# Motor_Encoders.net
KiCad netlist of a schematic drawn in Altium Designer
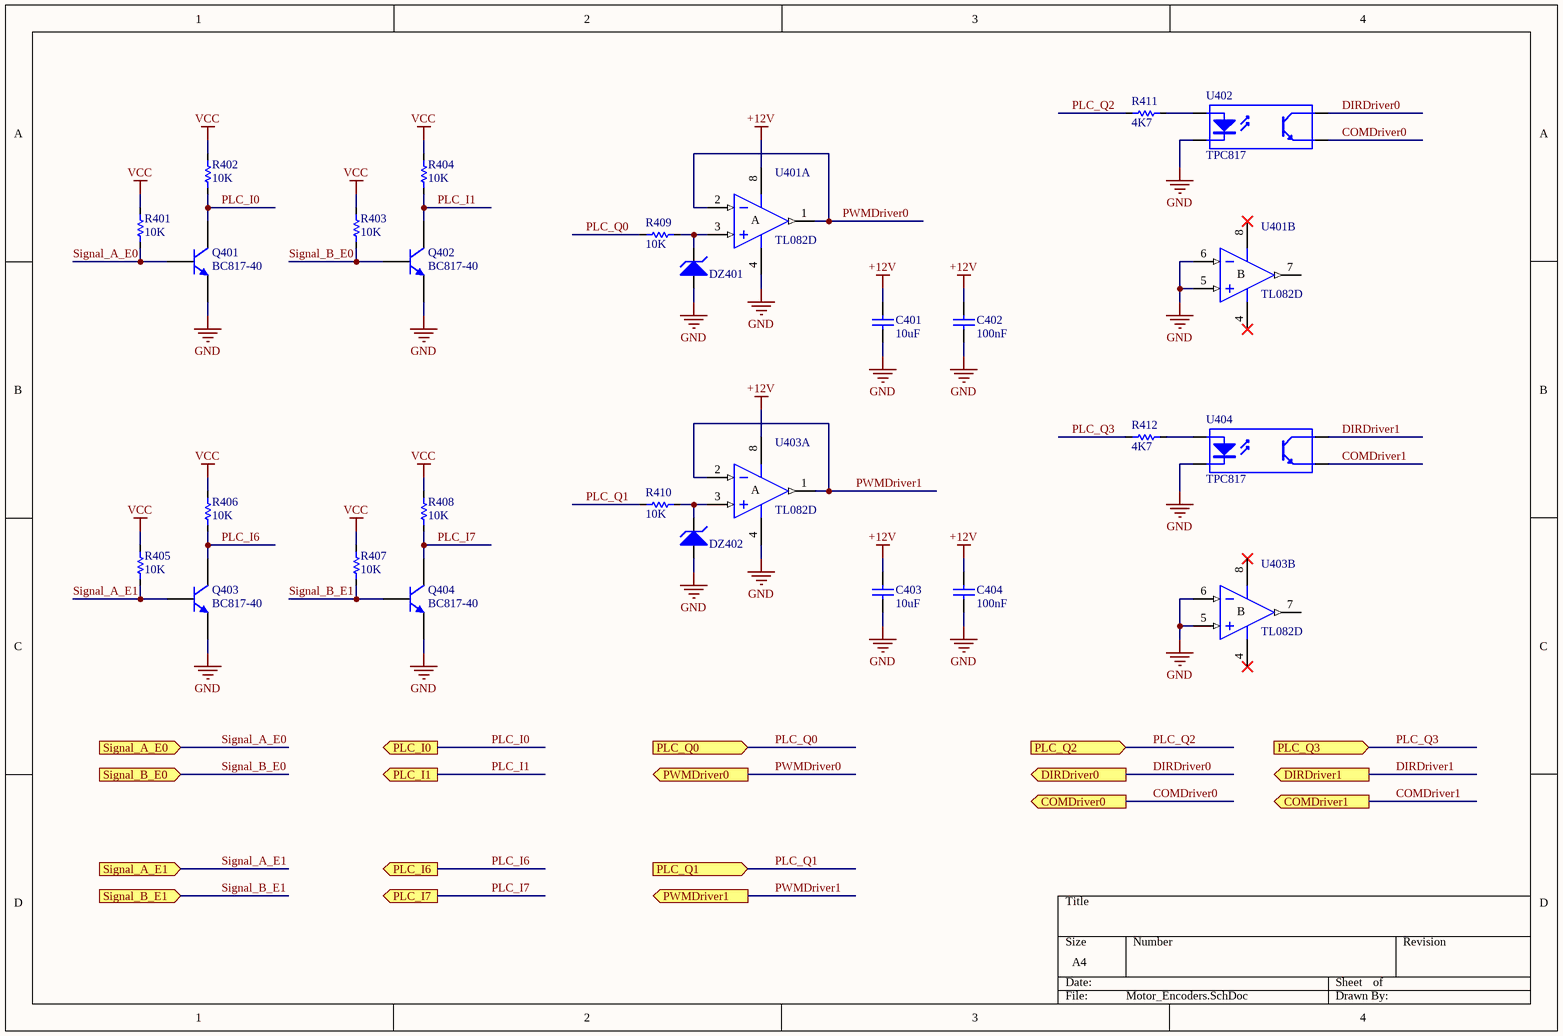
[diagram p0: Motor_Encoders.SchDoc]

(export (version "E")
  (design (tool "Eeschema 10.0.6"))
  (components
    (comp (ref "C401")
      (value "Cap Ceramico SMD")
      (footprint "C0603")
      (description "Cap Ceramico SMD 0805")
      (fields (field (name "VALOR") "10uF"))
      (libsource (lib "RUF-Dispositivos-Grales") (part "Cap Ceramico SMD"))
    )
    (comp (ref "C402")
      (value "Cap Ceramico SMD")
      (footprint "C0603")
      (description "Cap Ceramico SMD 0805")
      (fields (field (name "VALOR") "100nF"))
      (libsource (lib "RUF-Dispositivos-Grales") (part "Cap Ceramico SMD"))
    )
    (comp (ref "C403")
      (value "Cap Ceramico SMD")
      (footprint "C0603")
      (description "Cap Ceramico SMD 0805")
      (fields (field (name "VALOR") "10uF"))
      (libsource (lib "RUF-Dispositivos-Grales") (part "Cap Ceramico SMD"))
    )
    (comp (ref "C404")
      (value "Cap Ceramico SMD")
      (footprint "C0603")
      (description "Cap Ceramico SMD 0805")
      (fields (field (name "VALOR") "100nF"))
      (libsource (lib "RUF-Dispositivos-Grales") (part "Cap Ceramico SMD"))
    )
    (comp (ref "DZ401")
      (value "Diodo Zenner SMD")
      (footprint "SOD-80")
      (description "Diodo zenner SMD")
      (libsource (lib "RUF-Dispositivos-Grales") (part "Diodo Zenner SMD"))
    )
    (comp (ref "DZ402")
      (value "Diodo Zenner SMD")
      (footprint "SOD-80")
      (description "Diodo zenner SMD")
      (libsource (lib "RUF-Dispositivos-Grales") (part "Diodo Zenner SMD"))
    )
    (comp (ref "Q401")
      (value "BC817-40")
      (footprint "SOT23_M")
      (description "NPN General-purpose Transistor")
      (fields (field (name "PUBLISHER") "Altium Limited"))
      (libsource (lib "Philips Discrete BJT - Low Power") (part "BC817-40"))
    )
    (comp (ref "Q402")
      (value "BC817-40")
      (footprint "SOT23_M")
      (description "NPN General-purpose Transistor")
      (fields (field (name "PUBLISHER") "Altium Limited"))
      (libsource (lib "Philips Discrete BJT - Low Power") (part "BC817-40"))
    )
    (comp (ref "Q403")
      (value "BC817-40")
      (footprint "SOT23_M")
      (description "NPN General-purpose Transistor")
      (fields (field (name "PUBLISHER") "Altium Limited"))
      (libsource (lib "Philips Discrete BJT - Low Power") (part "BC817-40"))
    )
    (comp (ref "Q404")
      (value "BC817-40")
      (footprint "SOT23_M")
      (description "NPN General-purpose Transistor")
      (fields (field (name "PUBLISHER") "Altium Limited"))
      (libsource (lib "Philips Discrete BJT - Low Power") (part "BC817-40"))
    )
    (comp (ref "R401")
      (value "Res SMD")
      (footprint "R0603")
      (description "Res Smd")
      (fields (field (name "VALOR") "10K"))
      (libsource (lib "RUF-Dispositivos-Grales") (part "Res SMD"))
    )
    (comp (ref "R402")
      (value "Res SMD")
      (footprint "R0603")
      (description "Res Smd")
      (fields (field (name "VALOR") "10K"))
      (libsource (lib "RUF-Dispositivos-Grales") (part "Res SMD"))
    )
    (comp (ref "R403")
      (value "Res SMD")
      (footprint "R0603")
      (description "Res Smd")
      (fields (field (name "VALOR") "10K"))
      (libsource (lib "RUF-Dispositivos-Grales") (part "Res SMD"))
    )
    (comp (ref "R404")
      (value "Res SMD")
      (footprint "R0603")
      (description "Res Smd")
      (fields (field (name "VALOR") "10K"))
      (libsource (lib "RUF-Dispositivos-Grales") (part "Res SMD"))
    )
    (comp (ref "R405")
      (value "Res SMD")
      (footprint "R0603")
      (description "Res Smd")
      (fields (field (name "VALOR") "10K"))
      (libsource (lib "RUF-Dispositivos-Grales") (part "Res SMD"))
    )
    (comp (ref "R406")
      (value "Res SMD")
      (footprint "R0603")
      (description "Res Smd")
      (fields (field (name "VALOR") "10K"))
      (libsource (lib "RUF-Dispositivos-Grales") (part "Res SMD"))
    )
    (comp (ref "R407")
      (value "Res SMD")
      (footprint "R0603")
      (description "Res Smd")
      (fields (field (name "VALOR") "10K"))
      (libsource (lib "RUF-Dispositivos-Grales") (part "Res SMD"))
    )
    (comp (ref "R408")
      (value "Res SMD")
      (footprint "R0603")
      (description "Res Smd")
      (fields (field (name "VALOR") "10K"))
      (libsource (lib "RUF-Dispositivos-Grales") (part "Res SMD"))
    )
    (comp (ref "R409")
      (value "Res SMD")
      (footprint "R0603")
      (description "Res Smd")
      (fields (field (name "VALOR") "10K"))
      (libsource (lib "RUF-Dispositivos-Grales") (part "Res SMD"))
    )
    (comp (ref "R410")
      (value "Res SMD")
      (footprint "R0603")
      (description "Res Smd")
      (fields (field (name "VALOR") "10K"))
      (libsource (lib "RUF-Dispositivos-Grales") (part "Res SMD"))
    )
    (comp (ref "R411")
      (value "Res SMD")
      (footprint "R0603")
      (description "Res Smd")
      (fields (field (name "VALOR") "4K7"))
      (libsource (lib "RUF-Dispositivos-Grales") (part "Res SMD"))
    )
    (comp (ref "R412")
      (value "Res SMD")
      (footprint "R0603")
      (description "Res Smd")
      (fields (field (name "VALOR") "4K7"))
      (libsource (lib "RUF-Dispositivos-Grales") (part "Res SMD"))
    )
    (comp (ref "U401")
      (value "TL082D")
      (footprint "D008_L")
      (description "JFET-Input Operational Amplifier")
      (fields (field (name "PUBLISHER") "Altium Limited"))
      (libsource (lib "TI Operational Amplifier") (part "TL082D"))
    )
    (comp (ref "U402")
      (value "TPC817")
      (footprint "DIP-4")
      (description "4-Pin Phototransistor Optocoupler")
      (fields (field (name "PUBLISHER") "Altium Limited"))
      (libsource (lib "Miscellaneous Devices") (part "Optoisolator1"))
    )
    (comp (ref "U403")
      (value "TL082D")
      (footprint "D008_L")
      (description "JFET-Input Operational Amplifier")
      (fields (field (name "PUBLISHER") "Altium Limited"))
      (libsource (lib "TI Operational Amplifier") (part "TL082D"))
    )
    (comp (ref "U404")
      (value "TPC817")
      (footprint "DIP-4")
      (description "4-Pin Phototransistor Optocoupler")
      (fields (field (name "PUBLISHER") "Altium Limited"))
      (libsource (lib "Miscellaneous Devices") (part "Optoisolator1"))
    )
  )
  (nets
    (net (code "1") (name "+12V") (class "Default")
      (node (ref "C401") (pin "1") (pinfunction "1_1") (pintype "passive"))
      (node (ref "C402") (pin "1") (pinfunction "1_1") (pintype "passive"))
      (node (ref "C403") (pin "1") (pinfunction "1_1") (pintype "passive"))
      (node (ref "C404") (pin "1") (pinfunction "1_1") (pintype "passive"))
      (node (ref "U401") (pin "8") (pinfunction "V+_8") (pintype "power_in"))
      (node (ref "U403") (pin "8") (pinfunction "V+_8") (pintype "power_in"))
    )
    (net (code "2") (name "/COMDriver0") (class "Default")
      (node (ref "U402") (pin "3") (pinfunction "E_3") (pintype "passive"))
    )
    (net (code "3") (name "/COMDriver1") (class "Default")
      (node (ref "U404") (pin "3") (pinfunction "E_3") (pintype "passive"))
    )
    (net (code "4") (name "/DIRDriver0") (class "Default")
      (node (ref "U402") (pin "4") (pinfunction "C_4") (pintype "passive"))
    )
    (net (code "5") (name "/DIRDriver1") (class "Default")
      (node (ref "U404") (pin "4") (pinfunction "C_4") (pintype "passive"))
    )
    (net (code "6") (name "/PLC_I0") (class "Default")
      (node (ref "Q401") (pin "3") (pinfunction "C_3") (pintype "passive"))
      (node (ref "R402") (pin "2") (pinfunction "2_2") (pintype "passive"))
    )
    (net (code "7") (name "/PLC_I1") (class "Default")
      (node (ref "Q402") (pin "3") (pinfunction "C_3") (pintype "passive"))
      (node (ref "R404") (pin "2") (pinfunction "2_2") (pintype "passive"))
    )
    (net (code "8") (name "/PLC_I6") (class "Default")
      (node (ref "Q403") (pin "3") (pinfunction "C_3") (pintype "passive"))
      (node (ref "R406") (pin "2") (pinfunction "2_2") (pintype "passive"))
    )
    (net (code "9") (name "/PLC_I7") (class "Default")
      (node (ref "Q404") (pin "3") (pinfunction "C_3") (pintype "passive"))
      (node (ref "R408") (pin "2") (pinfunction "2_2") (pintype "passive"))
    )
    (net (code "10") (name "/PLC_Q0") (class "Default")
      (node (ref "R409") (pin "1") (pinfunction "1_1") (pintype "passive"))
    )
    (net (code "11") (name "/PLC_Q1") (class "Default")
      (node (ref "R410") (pin "1") (pinfunction "1_1") (pintype "passive"))
    )
    (net (code "12") (name "/PLC_Q2") (class "Default")
      (node (ref "R411") (pin "2") (pinfunction "2_2") (pintype "passive"))
    )
    (net (code "13") (name "/PLC_Q3") (class "Default")
      (node (ref "R412") (pin "2") (pinfunction "2_2") (pintype "passive"))
    )
    (net (code "14") (name "/PWMDriver0") (class "Default")
      (node (ref "U401") (pin "1") (pinfunction "OUT_1") (pintype "output"))
      (node (ref "U401") (pin "2") (pinfunction "IN-_2") (pintype "input"))
    )
    (net (code "15") (name "/PWMDriver1") (class "Default")
      (node (ref "U403") (pin "1") (pinfunction "OUT_1") (pintype "output"))
      (node (ref "U403") (pin "2") (pinfunction "IN-_2") (pintype "input"))
    )
    (net (code "16") (name "/Signal_A_E0") (class "Default")
      (node (ref "Q401") (pin "1") (pinfunction "B_1") (pintype "passive"))
      (node (ref "R401") (pin "2") (pinfunction "2_2") (pintype "passive"))
    )
    (net (code "17") (name "/Signal_A_E1") (class "Default")
      (node (ref "Q403") (pin "1") (pinfunction "B_1") (pintype "passive"))
      (node (ref "R405") (pin "2") (pinfunction "2_2") (pintype "passive"))
    )
    (net (code "18") (name "/Signal_B_E0") (class "Default")
      (node (ref "Q402") (pin "1") (pinfunction "B_1") (pintype "passive"))
      (node (ref "R403") (pin "2") (pinfunction "2_2") (pintype "passive"))
    )
    (net (code "19") (name "/Signal_B_E1") (class "Default")
      (node (ref "Q404") (pin "1") (pinfunction "B_1") (pintype "passive"))
      (node (ref "R407") (pin "2") (pinfunction "2_2") (pintype "passive"))
    )
    (net (code "20") (name "GND") (class "Default")
      (node (ref "C401") (pin "2") (pinfunction "2_2") (pintype "passive"))
      (node (ref "C402") (pin "2") (pinfunction "2_2") (pintype "passive"))
      (node (ref "C403") (pin "2") (pinfunction "2_2") (pintype "passive"))
      (node (ref "C404") (pin "2") (pinfunction "2_2") (pintype "passive"))
      (node (ref "DZ401") (pin "1") (pinfunction "A_1") (pintype "passive"))
      (node (ref "DZ402") (pin "1") (pinfunction "A_1") (pintype "passive"))
      (node (ref "Q401") (pin "2") (pinfunction "E_2") (pintype "passive"))
      (node (ref "Q402") (pin "2") (pinfunction "E_2") (pintype "passive"))
      (node (ref "Q403") (pin "2") (pinfunction "E_2") (pintype "passive"))
      (node (ref "Q404") (pin "2") (pinfunction "E_2") (pintype "passive"))
      (node (ref "U401") (pin "4") (pinfunction "V-_4") (pintype "power_in"))
      (node (ref "U401") (pin "5") (pinfunction "IN+_5") (pintype "input"))
      (node (ref "U401") (pin "6") (pinfunction "IN-_6") (pintype "input"))
      (node (ref "U402") (pin "2") (pinfunction "K_2") (pintype "passive"))
      (node (ref "U403") (pin "4") (pinfunction "V-_4") (pintype "power_in"))
      (node (ref "U403") (pin "5") (pinfunction "IN+_5") (pintype "input"))
      (node (ref "U403") (pin "6") (pinfunction "IN-_6") (pintype "input"))
      (node (ref "U404") (pin "2") (pinfunction "K_2") (pintype "passive"))
    )
    (net (code "21") (name "Net-(DZ401-K)") (class "Default")
      (node (ref "DZ401") (pin "2") (pinfunction "K_2") (pintype "passive"))
      (node (ref "R409") (pin "2") (pinfunction "2_2") (pintype "passive"))
      (node (ref "U401") (pin "3") (pinfunction "IN+_3") (pintype "input"))
    )
    (net (code "22") (name "Net-(DZ402-K)") (class "Default")
      (node (ref "DZ402") (pin "2") (pinfunction "K_2") (pintype "passive"))
      (node (ref "R410") (pin "2") (pinfunction "2_2") (pintype "passive"))
      (node (ref "U403") (pin "3") (pinfunction "IN+_3") (pintype "input"))
    )
    (net (code "23") (name "Net-(U402-A)") (class "Default")
      (node (ref "R411") (pin "1") (pinfunction "1_1") (pintype "passive"))
      (node (ref "U402") (pin "1") (pinfunction "A_1") (pintype "passive"))
    )
    (net (code "24") (name "Net-(U404-A)") (class "Default")
      (node (ref "R412") (pin "1") (pinfunction "1_1") (pintype "passive"))
      (node (ref "U404") (pin "1") (pinfunction "A_1") (pintype "passive"))
    )
    (net (code "25") (name "VCC") (class "Default")
      (node (ref "R401") (pin "1") (pinfunction "1_1") (pintype "passive"))
      (node (ref "R402") (pin "1") (pinfunction "1_1") (pintype "passive"))
      (node (ref "R403") (pin "1") (pinfunction "1_1") (pintype "passive"))
      (node (ref "R404") (pin "1") (pinfunction "1_1") (pintype "passive"))
      (node (ref "R405") (pin "1") (pinfunction "1_1") (pintype "passive"))
      (node (ref "R406") (pin "1") (pinfunction "1_1") (pintype "passive"))
      (node (ref "R407") (pin "1") (pinfunction "1_1") (pintype "passive"))
      (node (ref "R408") (pin "1") (pinfunction "1_1") (pintype "passive"))
    )
    (net (code "26") (name "unconnected-(U401B-OUT-Pad7)") (class "Default")
      (node (ref "U401") (pin "7") (pinfunction "OUT_7") (pintype "output"))
    )
    (net (code "27") (name "unconnected-(U401B-V+-Pad8)") (class "Default")
      (node (ref "U401") (pin "8") (pinfunction "V+_8") (pintype "power_in+no_connect"))
    )
    (net (code "28") (name "unconnected-(U401B-V--Pad4)") (class "Default")
      (node (ref "U401") (pin "4") (pinfunction "V-_4") (pintype "power_in+no_connect"))
    )
    (net (code "29") (name "unconnected-(U403B-OUT-Pad7)") (class "Default")
      (node (ref "U403") (pin "7") (pinfunction "OUT_7") (pintype "output"))
    )
    (net (code "30") (name "unconnected-(U403B-V+-Pad8)") (class "Default")
      (node (ref "U403") (pin "8") (pinfunction "V+_8") (pintype "power_in+no_connect"))
    )
    (net (code "31") (name "unconnected-(U403B-V--Pad4)") (class "Default")
      (node (ref "U403") (pin "4") (pinfunction "V-_4") (pintype "power_in+no_connect"))
    )
  )
)
